# in3controlpanel.net
KiCad netlist of a schematic drawn in EAGLE
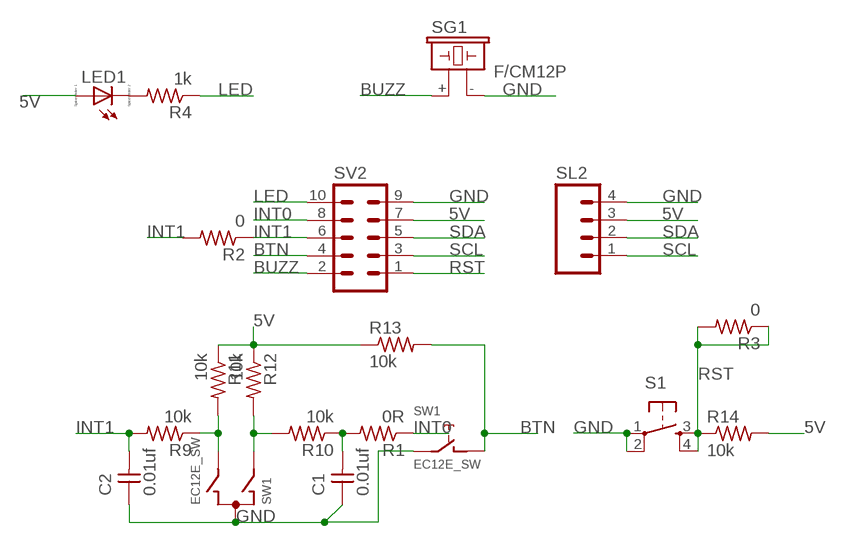
[diagram p0: schematic, sheet 1]

(export (version "E")
  (design (tool "Eeschema 10.0.6"))
  (components
    (comp (ref "C1")
      (value "0.01uf")
      (footprint "eagle-import:1206")
      (libsource (lib "eagle-import") (part "UNPOLARIZED_CAPACITOR1206"))
    )
    (comp (ref "C2")
      (value "0.01uf")
      (footprint "eagle-import:1206")
      (libsource (lib "eagle-import") (part "UNPOLARIZED_CAPACITOR1206"))
    )
    (comp (ref "LED1")
      (value "LED_E")
      (footprint "eagle-import:LED_1206")
      (libsource (lib "eagle-import") (part "LED_E"))
    )
    (comp (ref "R1")
      (value "0R")
      (footprint "eagle-import:1206")
      (libsource (lib "eagle-import") (part "RESISTOR1206"))
    )
    (comp (ref "R2")
      (value "0")
      (footprint "eagle-import:1206")
      (libsource (lib "eagle-import") (part "RESISTOR1206"))
    )
    (comp (ref "R3")
      (value "0")
      (footprint "eagle-import:1206")
      (libsource (lib "eagle-import") (part "RESISTOR1206"))
    )
    (comp (ref "R4")
      (value "1k")
      (footprint "eagle-import:1206")
      (libsource (lib "eagle-import") (part "RESISTOR1206"))
    )
    (comp (ref "R9")
      (value "10k")
      (footprint "eagle-import:1206")
      (libsource (lib "eagle-import") (part "RESISTOR1206"))
    )
    (comp (ref "R10")
      (value "10k")
      (footprint "eagle-import:1206")
      (libsource (lib "eagle-import") (part "RESISTOR1206"))
    )
    (comp (ref "R11")
      (value "10k")
      (footprint "eagle-import:1206")
      (libsource (lib "eagle-import") (part "RESISTOR1206"))
    )
    (comp (ref "R12")
      (value "10k")
      (footprint "eagle-import:1206")
      (libsource (lib "eagle-import") (part "RESISTOR1206"))
    )
    (comp (ref "R13")
      (value "10k")
      (footprint "eagle-import:1206")
      (libsource (lib "eagle-import") (part "RESISTOR1206"))
    )
    (comp (ref "R14")
      (value "10k")
      (footprint "eagle-import:1206")
      (libsource (lib "eagle-import") (part "RESISTOR1206"))
    )
    (comp (ref "S1")
      (value "6MM_SWITCH6MM_SWITCH")
      (footprint "eagle-import:6MM_SWITCH")
      (libsource (lib "eagle-import") (part "6MM_SWITCH6MM_SWITCH"))
    )
    (comp (ref "SG1")
      (value "F/CM12P")
      (footprint "eagle-import:F_CM12P")
      (libsource (lib "eagle-import") (part "F/CM12P"))
    )
    (comp (ref "SL2")
      (value "MA04")
      (footprint "eagle-import:04PA")
      (libsource (lib "eagle-import") (part "MA04"))
    )
    (comp (ref "SV2")
      (value "MA05-2")
      (footprint "eagle-import:MA05-2")
      (libsource (lib "eagle-import") (part "MA05-2"))
    )
    (comp (ref "SW1")
      (value "EC12E_SW")
      (footprint "eagle-import:ALPS_EC12E_SW")
      (fields (field (name "MPN") "EC12E2424407"))
      (libsource (lib "eagle-import") (part "EC12E_SW"))
    )
  )
  (nets
    (net (code "1") (name "/5V") (class "Default")
      (node (ref "LED1") (pin "A") (pinfunction "A_A") (pintype "passive"))
      (node (ref "R11") (pin "1") (pinfunction "1_1") (pintype "passive"))
      (node (ref "R12") (pin "1") (pinfunction "1_1") (pintype "passive"))
      (node (ref "R13") (pin "1") (pinfunction "1_1") (pintype "passive"))
      (node (ref "R14") (pin "2") (pinfunction "2_2") (pintype "passive"))
      (node (ref "SL2") (pin "3") (pinfunction "3_3") (pintype "passive"))
      (node (ref "SV2") (pin "7") (pinfunction "7_7") (pintype "passive"))
    )
    (net (code "2") (name "/BTN") (class "Default")
      (node (ref "R13") (pin "2") (pinfunction "2_2") (pintype "passive"))
      (node (ref "SV2") (pin "4") (pinfunction "4_4") (pintype "passive"))
      (node (ref "SW1") (pin "D") (pinfunction "1_D") (pintype "passive"))
    )
    (net (code "3") (name "/BUZZ") (class "Default")
      (node (ref "SG1") (pin "+") (pinfunction "1_+") (pintype "passive"))
      (node (ref "SV2") (pin "2") (pinfunction "2_2") (pintype "passive"))
    )
    (net (code "4") (name "/GND") (class "Default")
      (node (ref "C1") (pin "1") (pinfunction "1_1") (pintype "passive"))
      (node (ref "C2") (pin "1") (pinfunction "1_1") (pintype "passive"))
      (node (ref "S1") (pin "1") (pinfunction "P_1") (pintype "passive"))
      (node (ref "S1") (pin "2") (pinfunction "P1_2") (pintype "passive"))
      (node (ref "SG1") (pin "-") (pinfunction "2_-") (pintype "passive"))
      (node (ref "SL2") (pin "4") (pinfunction "4_4") (pintype "passive"))
      (node (ref "SV2") (pin "9") (pinfunction "9_9") (pintype "passive"))
      (node (ref "SW1") (pin "C") (pinfunction "C_C") (pintype "passive"))
      (node (ref "SW1") (pin "E") (pinfunction "2_E") (pintype "passive"))
    )
    (net (code "5") (name "/INT0") (class "Default")
      (node (ref "C1") (pin "2") (pinfunction "2_2") (pintype "passive"))
      (node (ref "R1") (pin "1") (pinfunction "1_1") (pintype "passive"))
      (node (ref "R1") (pin "2") (pinfunction "2_2") (pintype "passive"))
      (node (ref "R10") (pin "1") (pinfunction "1_1") (pintype "passive"))
      (node (ref "SV2") (pin "8") (pinfunction "8_8") (pintype "passive"))
    )
    (net (code "6") (name "/INT1") (class "Default")
      (node (ref "C2") (pin "2") (pinfunction "2_2") (pintype "passive"))
      (node (ref "R2") (pin "1") (pinfunction "1_1") (pintype "passive"))
      (node (ref "R2") (pin "2") (pinfunction "2_2") (pintype "passive"))
      (node (ref "R9") (pin "2") (pinfunction "2_2") (pintype "passive"))
      (node (ref "SV2") (pin "6") (pinfunction "6_6") (pintype "passive"))
    )
    (net (code "7") (name "/LED") (class "Default")
      (node (ref "R4") (pin "1") (pinfunction "1_1") (pintype "passive"))
      (node (ref "SV2") (pin "10") (pinfunction "10_10") (pintype "passive"))
    )
    (net (code "8") (name "/RST") (class "Default")
      (node (ref "R14") (pin "1") (pinfunction "1_1") (pintype "passive"))
      (node (ref "R3") (pin "1") (pinfunction "1_1") (pintype "passive"))
      (node (ref "R3") (pin "2") (pinfunction "2_2") (pintype "passive"))
      (node (ref "S1") (pin "3") (pinfunction "S_3") (pintype "passive"))
      (node (ref "S1") (pin "4") (pinfunction "S1_4") (pintype "passive"))
      (node (ref "SV2") (pin "1") (pinfunction "1_1") (pintype "passive"))
    )
    (net (code "9") (name "/SCL") (class "Default")
      (node (ref "SL2") (pin "1") (pinfunction "1_1") (pintype "passive"))
      (node (ref "SV2") (pin "3") (pinfunction "3_3") (pintype "passive"))
    )
    (net (code "10") (name "/SDA") (class "Default")
      (node (ref "SL2") (pin "2") (pinfunction "2_2") (pintype "passive"))
      (node (ref "SV2") (pin "5") (pinfunction "5_5") (pintype "passive"))
    )
    (net (code "11") (name "Net-(LED1-PadC)") (class "Default")
      (node (ref "LED1") (pin "C") (pinfunction "C_C") (pintype "passive"))
      (node (ref "R4") (pin "2") (pinfunction "2_2") (pintype "passive"))
    )
    (net (code "12") (name "Net-(R10-Pad2)") (class "Default")
      (node (ref "R10") (pin "2") (pinfunction "2_2") (pintype "passive"))
      (node (ref "R12") (pin "2") (pinfunction "2_2") (pintype "passive"))
      (node (ref "SW1") (pin "A") (pinfunction "A_A") (pintype "passive"))
    )
    (net (code "13") (name "Net-(R11-Pad2)") (class "Default")
      (node (ref "R11") (pin "2") (pinfunction "2_2") (pintype "passive"))
      (node (ref "R9") (pin "1") (pinfunction "1_1") (pintype "passive"))
      (node (ref "SW1") (pin "B") (pinfunction "B_B") (pintype "passive"))
    )
  )
)
